# Domino_Single_Ethernet_Overlap_No_Teardr.net
KiCad netlist of a schematic drawn in EAGLE
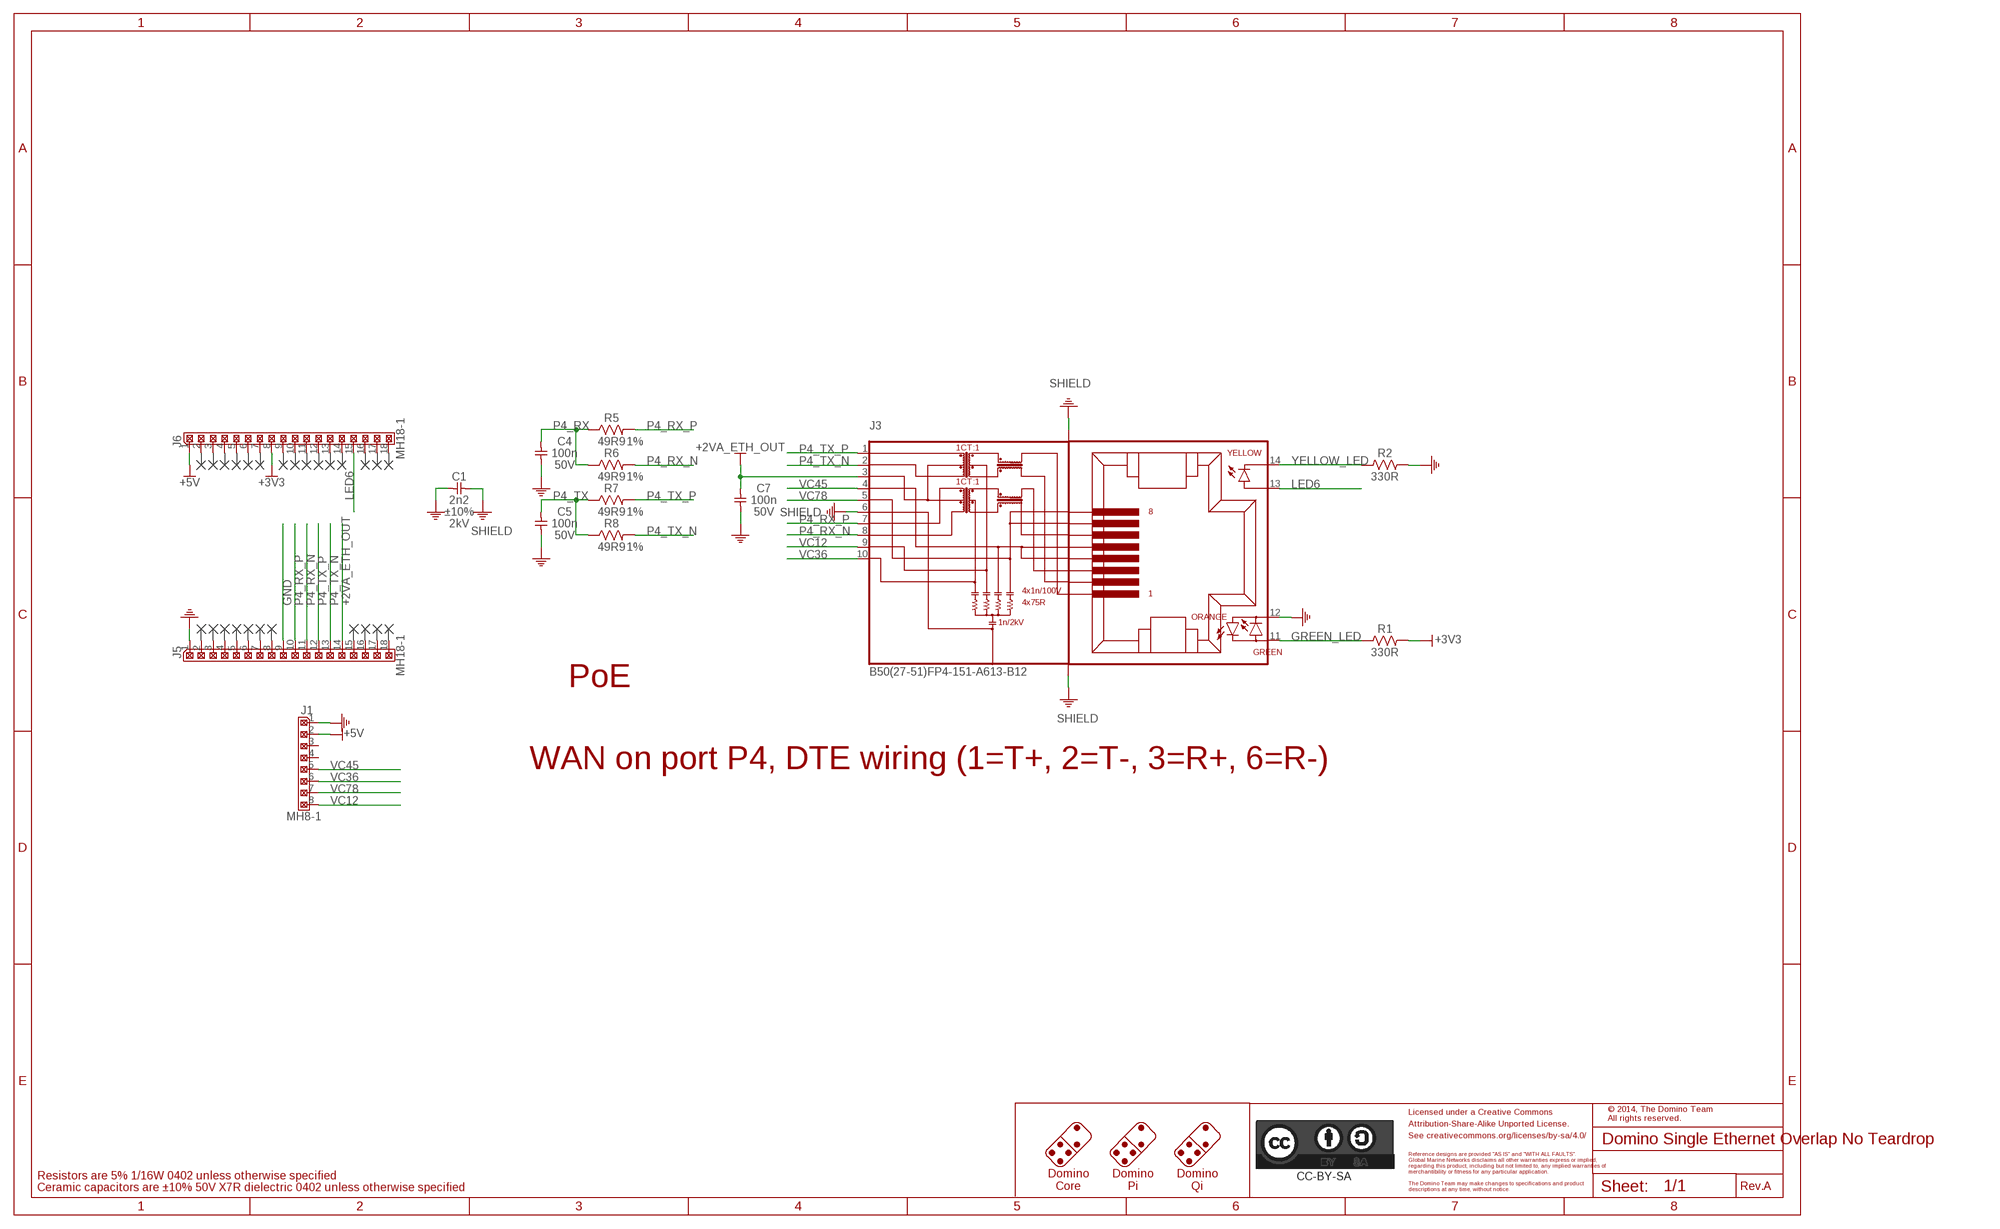
[diagram p0: schematic, sheet 1]

(export (version "E")
  (design (tool "Eeschema 10.0.6"))
  (components
    (comp (ref "C1")
      (value "2n2")
      (footprint "eagle-import:C1206")
      (fields
        (field (name "PARTNO") "C1210_2n2_X7R_10%_CER_2kV")
        (field (name "TOL") "±10%")
        (field (name "VOLT") "2kV")
      )
      (libsource (lib "eagle-import") (part "CAP_1206"))
    )
    (comp (ref "C4")
      (value "100n")
      (footprint "eagle-import:C0402")
      (fields (field (name "PARTNO") "C0402_100n_X7R_10%_CER_50V") (field (name "VOLT") "50V"))
      (libsource (lib "eagle-import") (part "CAP_0402"))
    )
    (comp (ref "C5")
      (value "100n")
      (footprint "eagle-import:C0402")
      (fields (field (name "PARTNO") "C0402_100n_X7R_10%_CER_50V") (field (name "VOLT") "50V"))
      (libsource (lib "eagle-import") (part "CAP_0402"))
    )
    (comp (ref "C7")
      (value "100n")
      (footprint "eagle-import:C0402")
      (fields (field (name "PARTNO") "C0402_100n_X7R_10%_CER_50V") (field (name "VOLT") "50V"))
      (libsource (lib "eagle-import") (part "CAP_0402"))
    )
    (comp (ref "CC-BY-SA1")
      (value "CC-BY-SA_LOGO")
      (footprint "eagle-import:CC-BY-SA_LOGO")
      (libsource (lib "eagle-import") (part "CC-BY-SA_LOGO"))
    )
    (comp (ref "J1")
      (value "MH8-1")
      (footprint "eagle-import:MH8-1-0.1")
      (libsource (lib "eagle-import") (part "MH8-1"))
    )
    (comp (ref "J3")
      (value "B50(27-51)FP4-151-A613-B12")
      (footprint "eagle-import:B50(27-51)FP4-151-A613-B12")
      (libsource (lib "eagle-import") (part "B50(27-51)FP4-151-A613-B12"))
    )
    (comp (ref "J5")
      (value "MH18-1")
      (footprint "eagle-import:MH18-1-0.1")
      (libsource (lib "eagle-import") (part "MH18-1"))
    )
    (comp (ref "J6")
      (value "MH18-1")
      (footprint "eagle-import:MH18-1-0.1")
      (libsource (lib "eagle-import") (part "MH18-1"))
    )
    (comp (ref "R1")
      (value "330R")
      (footprint "eagle-import:R0402")
      (fields (field (name "PARTNO") "R0402_330R_5%_62.5mW"))
      (libsource (lib "eagle-import") (part "RES_0402"))
    )
    (comp (ref "R2")
      (value "330R")
      (footprint "eagle-import:R0402")
      (fields (field (name "PARTNO") "R0402_330R_5%_62.5mW"))
      (libsource (lib "eagle-import") (part "RES_0402"))
    )
    (comp (ref "R5")
      (value "49R9")
      (footprint "eagle-import:R0402")
      (fields (field (name "PARTNO") "R0402_49R9_1%_62.5mW") (field (name "TOL") "1%"))
      (libsource (lib "eagle-import") (part "RES_0402"))
    )
    (comp (ref "R6")
      (value "49R9")
      (footprint "eagle-import:R0402")
      (fields (field (name "PARTNO") "R0402_49R9_1%_62.5mW") (field (name "TOL") "1%"))
      (libsource (lib "eagle-import") (part "RES_0402"))
    )
    (comp (ref "R7")
      (value "49R9")
      (footprint "eagle-import:R0402")
      (fields (field (name "PARTNO") "R0402_49R9_1%_62.5mW") (field (name "TOL") "1%"))
      (libsource (lib "eagle-import") (part "RES_0402"))
    )
    (comp (ref "R8")
      (value "49R9")
      (footprint "eagle-import:R0402")
      (fields (field (name "PARTNO") "R0402_49R9_1%_62.5mW") (field (name "TOL") "1%"))
      (libsource (lib "eagle-import") (part "RES_0402"))
    )
  )
  (nets
    (net (code "1") (name "+2VA_ETH_OUT") (class "Default")
      (node (ref "C7") (pin "2") (pinfunction "2_2") (pintype "passive"))
      (node (ref "J3") (pin "3") (pinfunction "3_3") (pintype "passive"))
      (node (ref "J5") (pin "14") (pinfunction "14_14") (pintype "passive"))
    )
    (net (code "2") (name "+3V3") (class "Default")
      (node (ref "J6") (pin "8") (pinfunction "8_8") (pintype "passive"))
      (node (ref "R1") (pin "2") (pinfunction "2_2") (pintype "passive"))
    )
    (net (code "3") (name "+5V") (class "Default")
      (node (ref "J1") (pin "2") (pinfunction "2_2") (pintype "passive"))
      (node (ref "J6") (pin "1") (pinfunction "1_1") (pintype "passive"))
    )
    (net (code "4") (name "/GREEN_LED") (class "Default")
      (node (ref "J3") (pin "11") (pinfunction "11_11") (pintype "passive"))
      (node (ref "R1") (pin "1") (pinfunction "1_1") (pintype "passive"))
    )
    (net (code "5") (name "/LED6") (class "Default")
      (node (ref "J3") (pin "13") (pinfunction "13_13") (pintype "passive"))
      (node (ref "J6") (pin "15") (pinfunction "15_15") (pintype "passive"))
    )
    (net (code "6") (name "/P4_RX") (class "Default")
      (node (ref "C4") (pin "2") (pinfunction "2_2") (pintype "passive"))
      (node (ref "R5") (pin "1") (pinfunction "1_1") (pintype "passive"))
      (node (ref "R6") (pin "1") (pinfunction "1_1") (pintype "passive"))
    )
    (net (code "7") (name "/P4_RX_N") (class "Default")
      (node (ref "J3") (pin "8") (pinfunction "8_8") (pintype "passive"))
      (node (ref "J5") (pin "11") (pinfunction "11_11") (pintype "passive"))
      (node (ref "R6") (pin "2") (pinfunction "2_2") (pintype "passive"))
    )
    (net (code "8") (name "/P4_RX_P") (class "Default")
      (node (ref "J3") (pin "7") (pinfunction "7_7") (pintype "passive"))
      (node (ref "J5") (pin "10") (pinfunction "10_10") (pintype "passive"))
      (node (ref "R5") (pin "2") (pinfunction "2_2") (pintype "passive"))
    )
    (net (code "9") (name "/P4_TX") (class "Default")
      (node (ref "C5") (pin "2") (pinfunction "2_2") (pintype "passive"))
      (node (ref "R7") (pin "1") (pinfunction "1_1") (pintype "passive"))
      (node (ref "R8") (pin "1") (pinfunction "1_1") (pintype "passive"))
    )
    (net (code "10") (name "/P4_TX_N") (class "Default")
      (node (ref "J3") (pin "2") (pinfunction "2_2") (pintype "passive"))
      (node (ref "J5") (pin "13") (pinfunction "13_13") (pintype "passive"))
      (node (ref "R8") (pin "2") (pinfunction "2_2") (pintype "passive"))
    )
    (net (code "11") (name "/P4_TX_P") (class "Default")
      (node (ref "J3") (pin "1") (pinfunction "1_1") (pintype "passive"))
      (node (ref "J5") (pin "12") (pinfunction "12_12") (pintype "passive"))
      (node (ref "R7") (pin "2") (pinfunction "2_2") (pintype "passive"))
    )
    (net (code "12") (name "/VC12") (class "Default")
      (node (ref "J1") (pin "8") (pinfunction "8_8") (pintype "passive"))
      (node (ref "J3") (pin "9") (pinfunction "9_9") (pintype "passive"))
    )
    (net (code "13") (name "/VC36") (class "Default")
      (node (ref "J1") (pin "6") (pinfunction "6_6") (pintype "passive"))
      (node (ref "J3") (pin "10") (pinfunction "10_10") (pintype "passive"))
    )
    (net (code "14") (name "/VC45") (class "Default")
      (node (ref "J1") (pin "5") (pinfunction "5_5") (pintype "passive"))
      (node (ref "J3") (pin "4") (pinfunction "4_4") (pintype "passive"))
    )
    (net (code "15") (name "/VC78") (class "Default")
      (node (ref "J1") (pin "7") (pinfunction "7_7") (pintype "passive"))
      (node (ref "J3") (pin "5") (pinfunction "5_5") (pintype "passive"))
    )
    (net (code "16") (name "/YELLOW_LED") (class "Default")
      (node (ref "J3") (pin "14") (pinfunction "14_14") (pintype "passive"))
      (node (ref "R2") (pin "1") (pinfunction "1_1") (pintype "passive"))
    )
    (net (code "17") (name "GND") (class "Default")
      (node (ref "C1") (pin "1") (pinfunction "1_1") (pintype "passive"))
      (node (ref "C4") (pin "1") (pinfunction "1_1") (pintype "passive"))
      (node (ref "C5") (pin "1") (pinfunction "1_1") (pintype "passive"))
      (node (ref "C7") (pin "1") (pinfunction "1_1") (pintype "passive"))
      (node (ref "J1") (pin "1") (pinfunction "1_1") (pintype "passive"))
      (node (ref "J3") (pin "12") (pinfunction "12_12") (pintype "passive"))
      (node (ref "J5") (pin "1") (pinfunction "1_1") (pintype "passive"))
      (node (ref "J5") (pin "9") (pinfunction "9_9") (pintype "passive"))
      (node (ref "R2") (pin "2") (pinfunction "2_2") (pintype "passive"))
    )
    (net (code "18") (name "SHIELD") (class "Default")
      (node (ref "C1") (pin "2") (pinfunction "2_2") (pintype "passive"))
      (node (ref "J3") (pin "6") (pinfunction "6_6") (pintype "power_in"))
      (node (ref "J3") (pin "SH$1") (pinfunction "SHIELD_SH$1") (pintype "power_in"))
      (node (ref "J3") (pin "SH$2") (pinfunction "SHIELD_SH$2") (pintype "power_in"))
    )
    (net (code "19") (name "unconnected-(J1-Pad3)") (class "Default")
      (node (ref "J1") (pin "3") (pinfunction "3_3") (pintype "passive"))
    )
    (net (code "20") (name "unconnected-(J1-Pad4)") (class "Default")
      (node (ref "J1") (pin "4") (pinfunction "4_4") (pintype "passive"))
    )
    (net (code "21") (name "unconnected-(J5-Pad2)") (class "Default")
      (node (ref "J5") (pin "2") (pinfunction "2_2") (pintype "passive"))
    )
    (net (code "22") (name "unconnected-(J5-Pad3)") (class "Default")
      (node (ref "J5") (pin "3") (pinfunction "3_3") (pintype "passive"))
    )
    (net (code "23") (name "unconnected-(J5-Pad4)") (class "Default")
      (node (ref "J5") (pin "4") (pinfunction "4_4") (pintype "passive"))
    )
    (net (code "24") (name "unconnected-(J5-Pad5)") (class "Default")
      (node (ref "J5") (pin "5") (pinfunction "5_5") (pintype "passive"))
    )
    (net (code "25") (name "unconnected-(J5-Pad6)") (class "Default")
      (node (ref "J5") (pin "6") (pinfunction "6_6") (pintype "passive"))
    )
    (net (code "26") (name "unconnected-(J5-Pad7)") (class "Default")
      (node (ref "J5") (pin "7") (pinfunction "7_7") (pintype "passive"))
    )
    (net (code "27") (name "unconnected-(J5-Pad8)") (class "Default")
      (node (ref "J5") (pin "8") (pinfunction "8_8") (pintype "passive"))
    )
    (net (code "28") (name "unconnected-(J5-Pad15)") (class "Default")
      (node (ref "J5") (pin "15") (pinfunction "15_15") (pintype "passive"))
    )
    (net (code "29") (name "unconnected-(J5-Pad16)") (class "Default")
      (node (ref "J5") (pin "16") (pinfunction "16_16") (pintype "passive"))
    )
    (net (code "30") (name "unconnected-(J5-Pad17)") (class "Default")
      (node (ref "J5") (pin "17") (pinfunction "17_17") (pintype "passive"))
    )
    (net (code "31") (name "unconnected-(J5-Pad18)") (class "Default")
      (node (ref "J5") (pin "18") (pinfunction "18_18") (pintype "passive"))
    )
    (net (code "32") (name "unconnected-(J6-Pad2)") (class "Default")
      (node (ref "J6") (pin "2") (pinfunction "2_2") (pintype "passive"))
    )
    (net (code "33") (name "unconnected-(J6-Pad3)") (class "Default")
      (node (ref "J6") (pin "3") (pinfunction "3_3") (pintype "passive"))
    )
    (net (code "34") (name "unconnected-(J6-Pad4)") (class "Default")
      (node (ref "J6") (pin "4") (pinfunction "4_4") (pintype "passive"))
    )
    (net (code "35") (name "unconnected-(J6-Pad5)") (class "Default")
      (node (ref "J6") (pin "5") (pinfunction "5_5") (pintype "passive"))
    )
    (net (code "36") (name "unconnected-(J6-Pad6)") (class "Default")
      (node (ref "J6") (pin "6") (pinfunction "6_6") (pintype "passive"))
    )
    (net (code "37") (name "unconnected-(J6-Pad7)") (class "Default")
      (node (ref "J6") (pin "7") (pinfunction "7_7") (pintype "passive"))
    )
    (net (code "38") (name "unconnected-(J6-Pad9)") (class "Default")
      (node (ref "J6") (pin "9") (pinfunction "9_9") (pintype "passive"))
    )
    (net (code "39") (name "unconnected-(J6-Pad10)") (class "Default")
      (node (ref "J6") (pin "10") (pinfunction "10_10") (pintype "passive"))
    )
    (net (code "40") (name "unconnected-(J6-Pad11)") (class "Default")
      (node (ref "J6") (pin "11") (pinfunction "11_11") (pintype "passive"))
    )
    (net (code "41") (name "unconnected-(J6-Pad12)") (class "Default")
      (node (ref "J6") (pin "12") (pinfunction "12_12") (pintype "passive"))
    )
    (net (code "42") (name "unconnected-(J6-Pad13)") (class "Default")
      (node (ref "J6") (pin "13") (pinfunction "13_13") (pintype "passive"))
    )
    (net (code "43") (name "unconnected-(J6-Pad14)") (class "Default")
      (node (ref "J6") (pin "14") (pinfunction "14_14") (pintype "passive"))
    )
    (net (code "44") (name "unconnected-(J6-Pad16)") (class "Default")
      (node (ref "J6") (pin "16") (pinfunction "16_16") (pintype "passive"))
    )
    (net (code "45") (name "unconnected-(J6-Pad17)") (class "Default")
      (node (ref "J6") (pin "17") (pinfunction "17_17") (pintype "passive"))
    )
    (net (code "46") (name "unconnected-(J6-Pad18)") (class "Default")
      (node (ref "J6") (pin "18") (pinfunction "18_18") (pintype "passive"))
    )
  )
)
